# Sheet1.net
KiCad netlist of a schematic drawn in Altium Designer
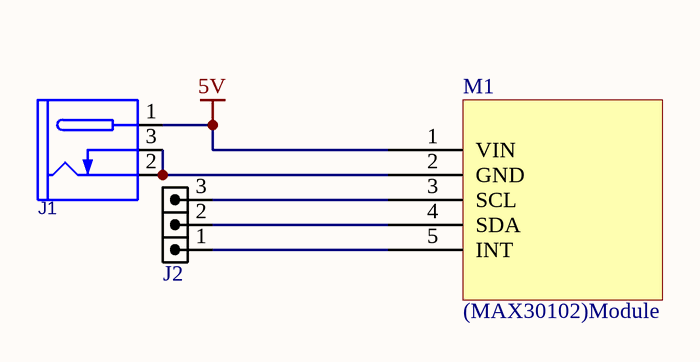
[diagram p0: Sheet1.SchDoc]

(export (version "E")
  (design (tool "Eeschema 10.0.6"))
  (components
    (comp (ref "J1")
      (value "DC_POWER_JACK")
      (footprint "JAC_PWR1")
      (description "CONN, PWR JACK DC, PLUG DIAM 1.0MM RA THD")
      (fields (field (name "MANF") "CUI STACK") (field (name "MANF_P#") "PJ-031CH, PJ-031C"))
      (libsource (lib "conn_powerJack") (part "CONN_PWR_JACKR1"))
    )
    (comp (ref "J2")
      (value "HDRM3")
      (footprint "HDR_M_1X3")
      (description "CONN, HEADER, Male, pitch: 2.54mm, 3POS")
      (libsource (lib "conn_header_2.54mm_st") (part "HDR_M_1X3"))
    )
    (comp (ref "M1")
      (value "(MAX30102)Module")
      (footprint "MODULE-MAX30102")
      (description "Heart Rate Sensor Module (MAX30102)")
      (libsource (lib "Schlib1") (part "MODULE-MAX30102"))
    )
  )
  (nets
    (net (code "1") (name "5V") (class "Default")
      (node (ref "J1") (pin "1") (pinfunction "TIP_1") (pintype "power_in"))
      (node (ref "M1") (pin "1") (pinfunction "VIN_1") (pintype "passive"))
    )
    (net (code "2") (name "Net-(J1-INSERTION_DET)") (class "Default")
      (node (ref "J1") (pin "2") (pinfunction "SLEEVE_2") (pintype "power_in"))
      (node (ref "J1") (pin "3") (pinfunction "INSERTION_DET_3") (pintype "power_in"))
      (node (ref "M1") (pin "2") (pinfunction "GND_2") (pintype "passive"))
    )
    (net (code "3") (name "Net-(M1-INT)") (class "Default")
      (node (ref "J2") (pin "1") (pinfunction "1_1") (pintype "passive"))
      (node (ref "M1") (pin "5") (pinfunction "INT_5") (pintype "passive"))
    )
    (net (code "4") (name "Net-(M1-SCL)") (class "Default")
      (node (ref "J2") (pin "3") (pinfunction "3_3") (pintype "passive"))
      (node (ref "M1") (pin "3") (pinfunction "SCL_3") (pintype "passive"))
    )
    (net (code "5") (name "Net-(M1-SDA)") (class "Default")
      (node (ref "J2") (pin "2") (pinfunction "2_2") (pintype "passive"))
      (node (ref "M1") (pin "4") (pinfunction "SDA_4") (pintype "passive"))
    )
  )
)
